# PLD_RadFET_Differential_Lowpass.net
KiCad netlist of a schematic drawn in Altium Designer
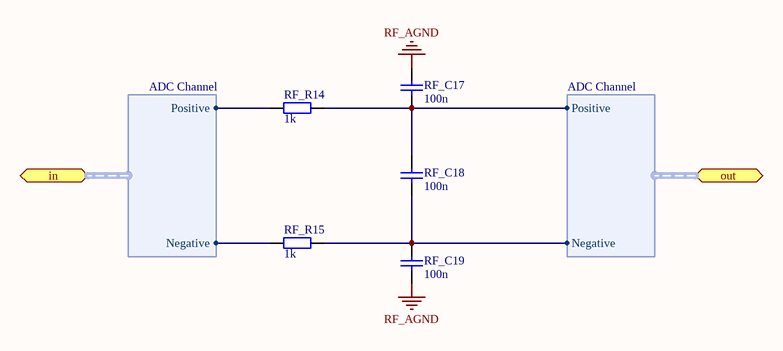
[diagram p0: PLD_RadFET_Differential_Lowpass.SchDoc]

(export (version "E")
  (design (tool "Eeschema 10.0.6"))
  (components
    (comp (ref "RF_C17")
      (value "100n")
      (footprint "SMD_Capacitor_0603")
      (description "Cap")
      (libsource (lib "capacitors") (part "Cap"))
    )
    (comp (ref "RF_C18")
      (value "100n")
      (footprint "SMD_Capacitor_0603")
      (description "Cap")
      (libsource (lib "capacitors") (part "Cap"))
    )
    (comp (ref "RF_C19")
      (value "100n")
      (footprint "SMD_Capacitor_0603")
      (description "Cap")
      (libsource (lib "capacitors") (part "Cap"))
    )
    (comp (ref "RF_R14")
      (value "1k")
      (footprint "SMD_Resistor_0603")
      (libsource (lib "resistors") (part "Res"))
    )
    (comp (ref "RF_R15")
      (value "1k")
      (footprint "SMD_Resistor_0603")
      (libsource (lib "resistors") (part "Res"))
    )
  )
  (nets
    (net (code "4") (name "Net-(RF_C17-Pad2)") (class "Default")
      (node (ref "RF_C17") (pin "2") (pinfunction "2_2") (pintype "passive"))
      (node (ref "RF_C18") (pin "1") (pinfunction "1_1") (pintype "passive"))
      (node (ref "RF_R14") (pin "2") (pinfunction "2_2") (pintype "passive"))
    )
    (net (code "5") (name "Net-(RF_C18-Pad2)") (class "Default")
      (node (ref "RF_C18") (pin "2") (pinfunction "2_2") (pintype "passive"))
      (node (ref "RF_C19") (pin "1") (pinfunction "1_1") (pintype "passive"))
      (node (ref "RF_R15") (pin "2") (pinfunction "2_2") (pintype "passive"))
    )
    (net (code "6") (name "RF_AGND") (class "Default")
      (node (ref "RF_C17") (pin "1") (pinfunction "1_1") (pintype "passive"))
      (node (ref "RF_C19") (pin "2") (pinfunction "2_2") (pintype "passive"))
    )
    (net (code "7") (name "unconnected-(RF_R14-Pad1)") (class "Default")
      (node (ref "RF_R14") (pin "1") (pinfunction "1_1") (pintype "passive"))
    )
    (net (code "8") (name "unconnected-(RF_R15-Pad1)") (class "Default")
      (node (ref "RF_R15") (pin "1") (pinfunction "1_1") (pintype "passive"))
    )
  )
)
